# powerblade_4v0.net
KiCad netlist of a schematic drawn in EAGLE
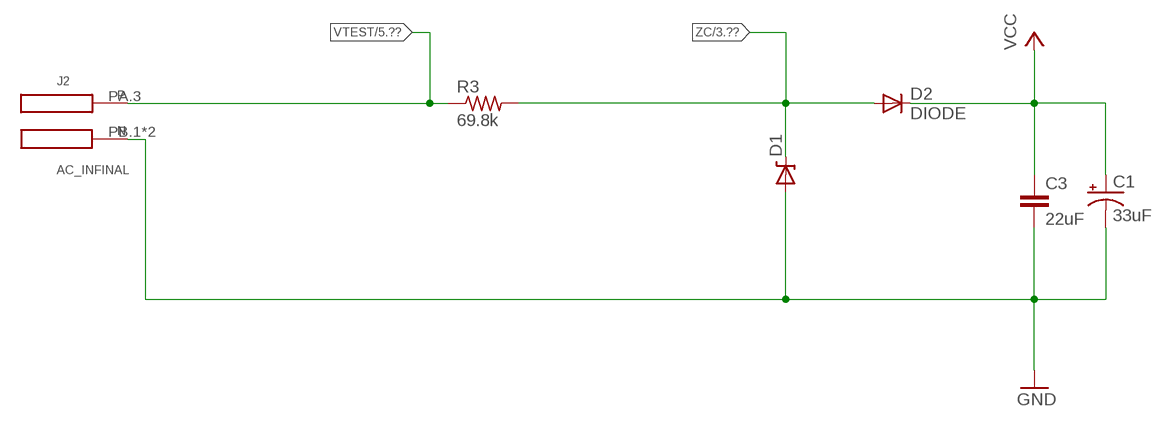
[diagram p0: schematic, sheet 1]
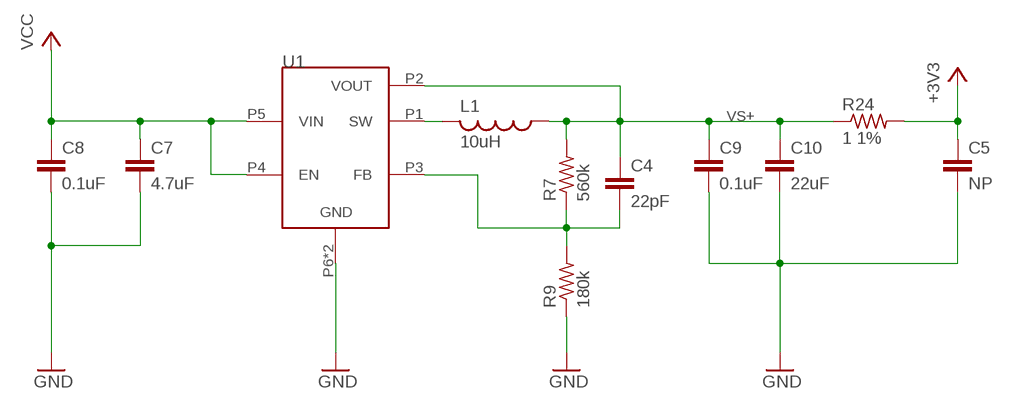
[diagram p1: schematic, sheet 2]
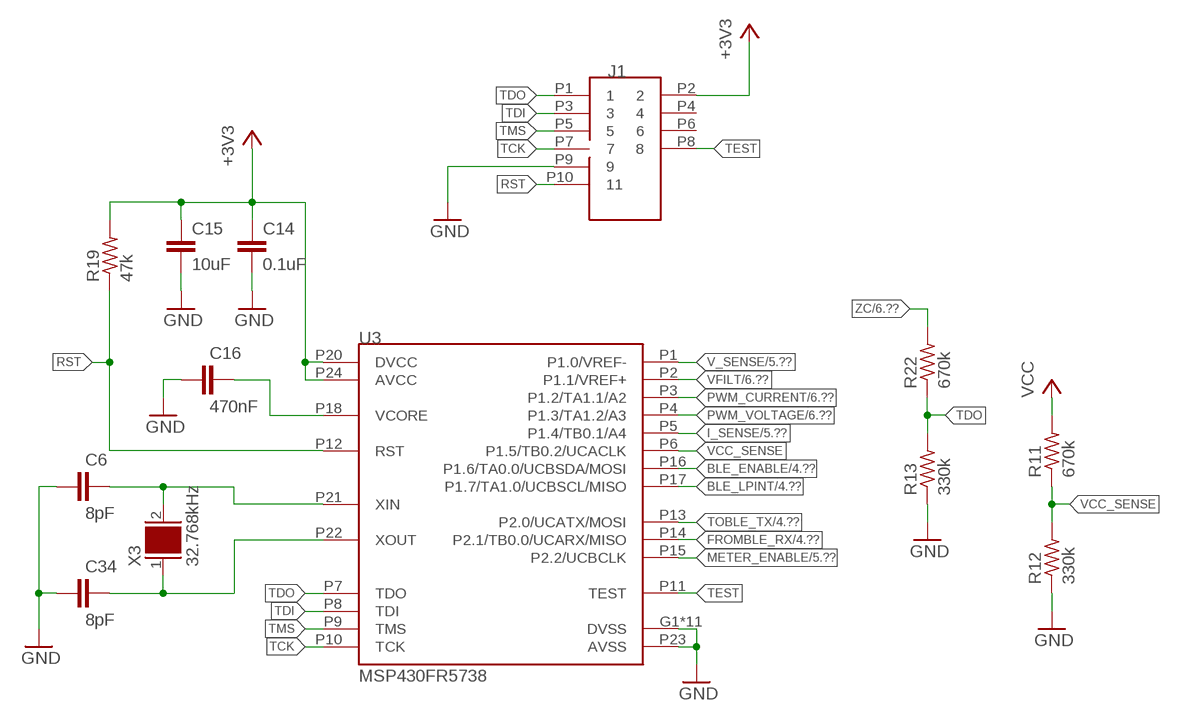
[diagram p2: schematic, sheet 3]
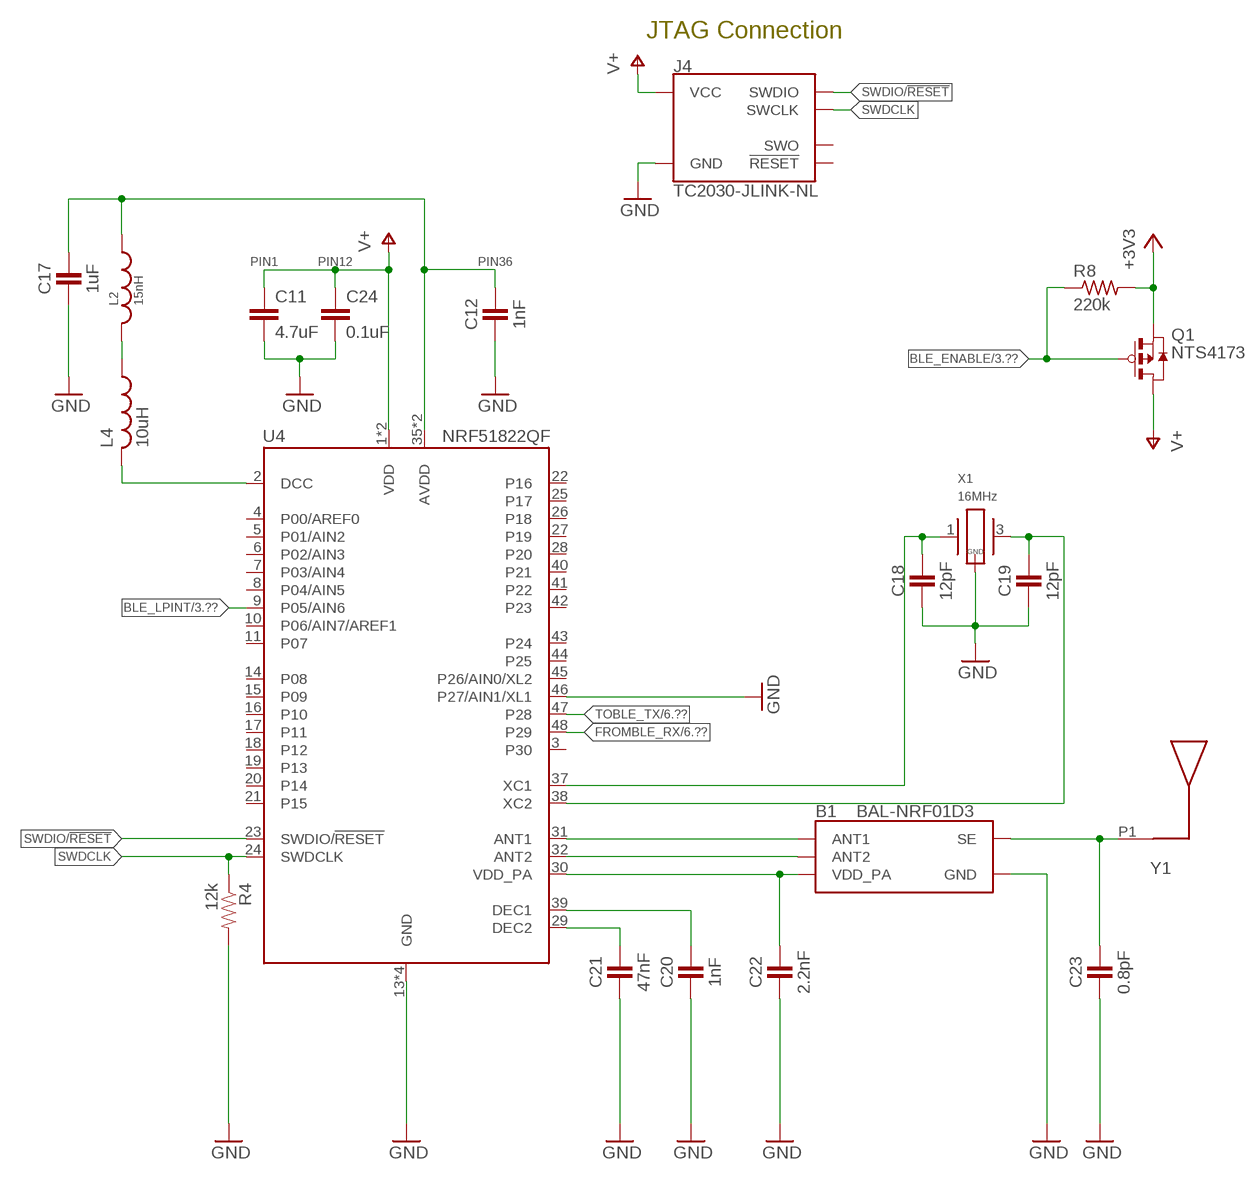
[diagram p3: schematic, sheet 4]
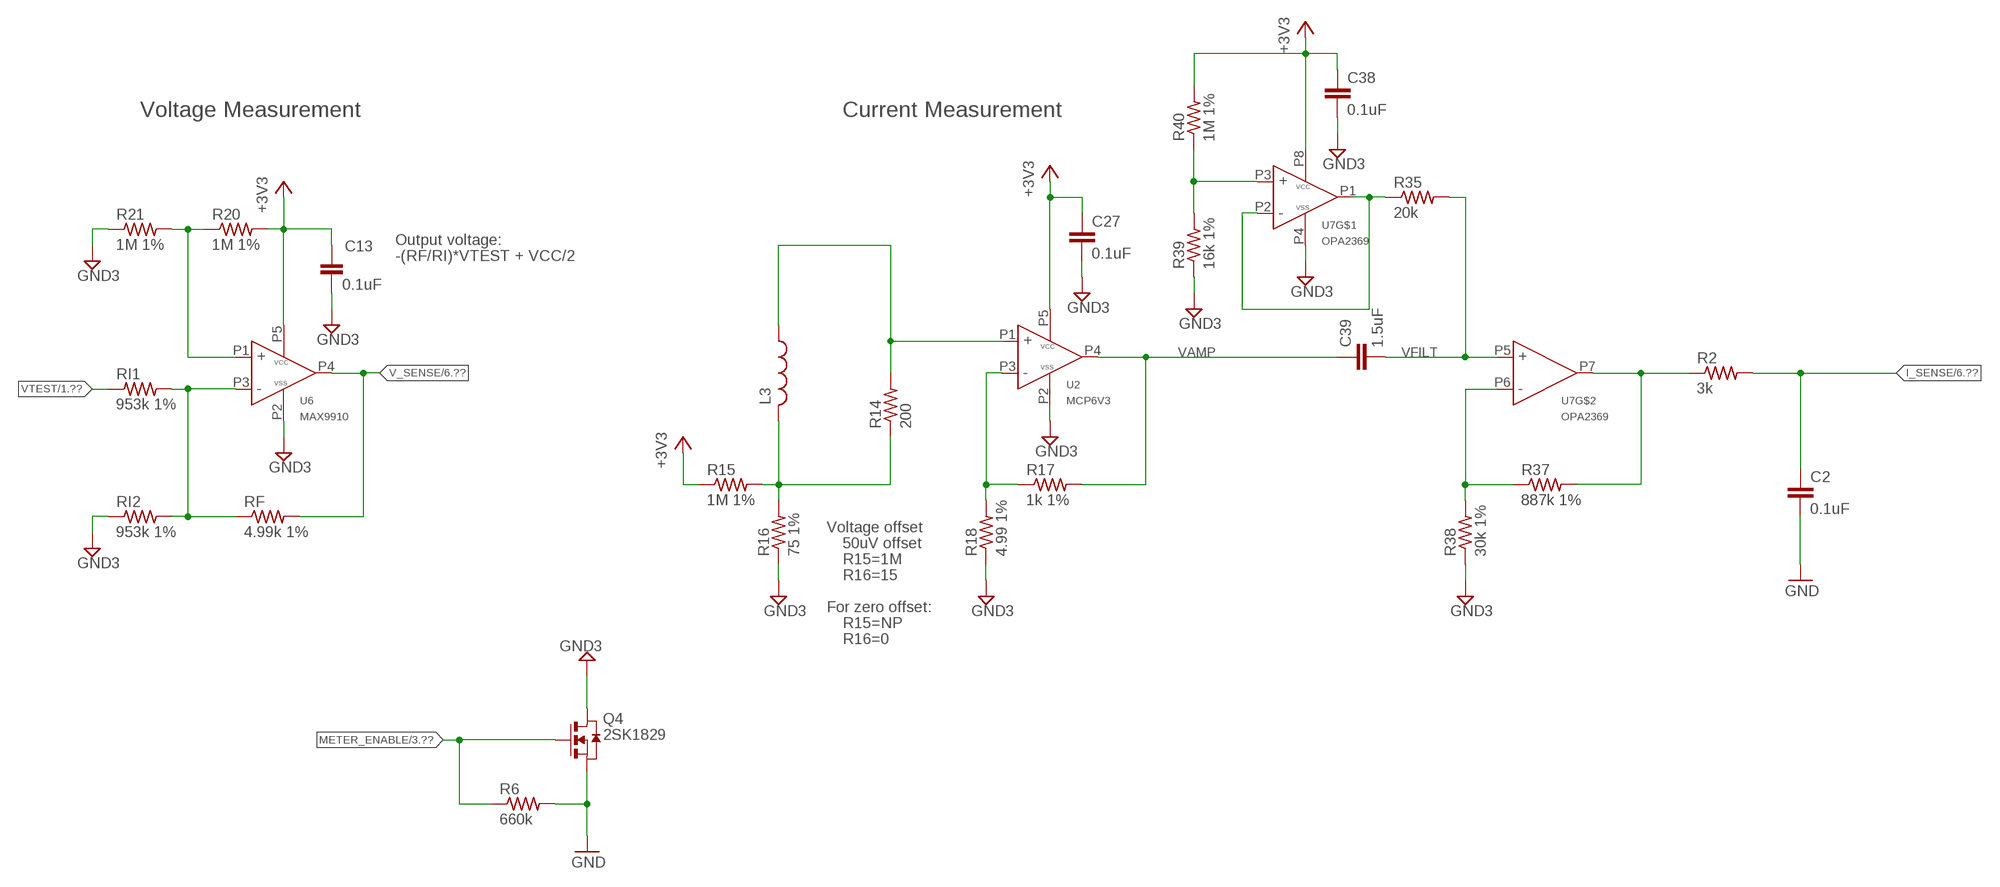
[diagram p4: schematic, sheet 5]
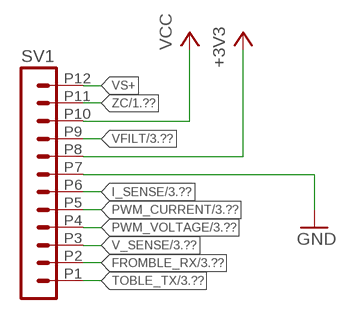
[diagram p5: schematic, sheet 6]

(export (version "E")
  (design (tool "Eeschema 10.0.6"))
  (components
    (comp (ref "C2")
      (value "0.1uF")
      (footprint "eagle-import:C0402")
      (libsource (lib "eagle-import") (part "C-EUC0402"))
    )
    (comp (ref "C13")
      (value "0.1uF")
      (footprint "eagle-import:0402_CAP")
      (libsource (lib "eagle-import") (part "CAPACITOR"))
    )
    (comp (ref "C27")
      (value "0.1uF")
      (footprint "eagle-import:C0402")
      (libsource (lib "eagle-import") (part "C-EUC0402"))
    )
    (comp (ref "C38")
      (value "0.1uF")
      (footprint "eagle-import:C0402")
      (libsource (lib "eagle-import") (part "C-EUC0402"))
    )
    (comp (ref "C39")
      (value "1.5uF")
      (footprint "eagle-import:C0402")
      (libsource (lib "eagle-import") (part "C-EUC0402"))
    )
    (comp (ref "L3")
      (value "L-USL0805")
      (footprint "eagle-import:L0805")
      (libsource (lib "eagle-import") (part "L-USL0805"))
    )
    (comp (ref "Q4")
      (value "2SK1829")
      (footprint "eagle-import:SC-70-3")
      (libsource (lib "eagle-import") (part "2SK1829"))
    )
    (comp (ref "R2")
      (value "3k")
      (footprint "eagle-import:R0402_SM")
      (libsource (lib "eagle-import") (part "R-US_R0402_SM"))
    )
    (comp (ref "R6")
      (value "660k")
      (footprint "eagle-import:R0402")
      (libsource (lib "eagle-import") (part "R-US_R0402"))
    )
    (comp (ref "R14")
      (value "200")
      (footprint "eagle-import:R0402")
      (libsource (lib "eagle-import") (part "R-US_R0402"))
    )
    (comp (ref "R15")
      (value "1M 1%")
      (footprint "eagle-import:R0402")
      (libsource (lib "eagle-import") (part "R-US_R0402"))
    )
    (comp (ref "R16")
      (value "75 1%")
      (footprint "eagle-import:R0402")
      (libsource (lib "eagle-import") (part "R-US_R0402"))
    )
    (comp (ref "R17")
      (value "1k 1%")
      (footprint "eagle-import:R0402")
      (libsource (lib "eagle-import") (part "R-US_R0402"))
    )
    (comp (ref "R18")
      (value "4.99 1%")
      (footprint "eagle-import:R0402")
      (libsource (lib "eagle-import") (part "R-US_R0402"))
    )
    (comp (ref "R20")
      (value "1M 1%")
      (footprint "eagle-import:R0402")
      (libsource (lib "eagle-import") (part "R-US_R0402"))
    )
    (comp (ref "R21")
      (value "1M 1%")
      (footprint "eagle-import:R0402_SM")
      (libsource (lib "eagle-import") (part "R-US_R0402_SM"))
    )
    (comp (ref "R35")
      (value "20k")
      (footprint "eagle-import:R0402")
      (libsource (lib "eagle-import") (part "R-US_R0402"))
    )
    (comp (ref "R37")
      (value "887k 1%")
      (footprint "eagle-import:R0402")
      (libsource (lib "eagle-import") (part "R-US_R0402"))
    )
    (comp (ref "R38")
      (value "30k 1%")
      (footprint "eagle-import:R0402")
      (libsource (lib "eagle-import") (part "R-US_R0402"))
    )
    (comp (ref "R39")
      (value "16k 1%")
      (footprint "eagle-import:R0402")
      (libsource (lib "eagle-import") (part "R-US_R0402"))
    )
    (comp (ref "R40")
      (value "1M 1%")
      (footprint "eagle-import:R0402")
      (libsource (lib "eagle-import") (part "R-US_R0402"))
    )
    (comp (ref "RF")
      (value "4.99k 1%")
      (footprint "eagle-import:R0402")
      (libsource (lib "eagle-import") (part "R-US_R0402"))
    )
    (comp (ref "RI1")
      (value "953k 1%")
      (footprint "eagle-import:R0402")
      (libsource (lib "eagle-import") (part "R-US_R0402"))
    )
    (comp (ref "RI2")
      (value "953k 1%")
      (footprint "eagle-import:R0402")
      (libsource (lib "eagle-import") (part "R-US_R0402"))
    )
    (comp (ref "U2")
      (value "MCP6V3")
      (footprint "eagle-import:SC70-5")
      (fields (field (name "DIGIKEY") "296-19547-1-ND"))
      (libsource (lib "eagle-import") (part "MCP6V3"))
    )
    (comp (ref "U6")
      (value "MAX9910")
      (footprint "eagle-import:SC70-5")
      (fields (field (name "DIGIKEY") "296-25252-1-ND"))
      (libsource (lib "eagle-import") (part "MAX9910"))
    )
    (comp (ref "U7")
      (value "OPA2369")
      (footprint "eagle-import:SOT-23-8")
      (libsource (lib "eagle-import") (part "OPA2369"))
    )
    (comp (ref "C6")
      (value "8pF")
      (footprint "eagle-import:C0402")
      (libsource (lib "eagle-import") (part "C-EUC0402"))
    )
    (comp (ref "C14")
      (value "0.1uF")
      (footprint "eagle-import:C0402")
      (libsource (lib "eagle-import") (part "C-EUC0402"))
    )
    (comp (ref "C15")
      (value "10uF")
      (footprint "eagle-import:C0603_SM")
      (libsource (lib "eagle-import") (part "C-EUC0603_SM"))
    )
    (comp (ref "C16")
      (value "470nF")
      (footprint "eagle-import:C0402")
      (libsource (lib "eagle-import") (part "C-EUC0402"))
    )
    (comp (ref "C34")
      (value "8pF")
      (footprint "eagle-import:C0402")
      (libsource (lib "eagle-import") (part "C-EUC0402"))
    )
    (comp (ref "J1")
      (value "JTAG_14PIN_IDC-ND")
      (footprint "eagle-import:TC2050-IDC-NL-430-ND")
      (libsource (lib "eagle-import") (part "JTAG_14PIN_IDC-ND"))
    )
    (comp (ref "R11")
      (value "670k")
      (footprint "eagle-import:R0402")
      (libsource (lib "eagle-import") (part "R-US_R0402"))
    )
    (comp (ref "R12")
      (value "330k")
      (footprint "eagle-import:R0402")
      (libsource (lib "eagle-import") (part "R-US_R0402"))
    )
    (comp (ref "R13")
      (value "330k")
      (footprint "eagle-import:R0402")
      (libsource (lib "eagle-import") (part "R-US_R0402"))
    )
    (comp (ref "R19")
      (value "47k")
      (footprint "eagle-import:R0402")
      (libsource (lib "eagle-import") (part "R-US_R0402"))
    )
    (comp (ref "R22")
      (value "670k")
      (footprint "eagle-import:R0402")
      (libsource (lib "eagle-import") (part "R-US_R0402"))
    )
    (comp (ref "U3")
      (value "MSP430FR5738")
      (footprint "eagle-import:VQFN-24")
      (libsource (lib "eagle-import") (part "MSP430FR5738"))
    )
    (comp (ref "X3")
      (value "32.768kHz")
      (footprint "eagle-import:0805")
      (libsource (lib "eagle-import") (part "CRYSTAL_0805"))
    )
    (comp (ref "B1")
      (value "BAL-NRF01D3")
      (footprint "eagle-import:BAL-NRF01D3")
      (libsource (lib "eagle-import") (part "BAL-NRF01D3"))
    )
    (comp (ref "C11")
      (value "4.7uF")
      (footprint "eagle-import:C0402")
      (libsource (lib "eagle-import") (part "C-EUC0402"))
    )
    (comp (ref "C12")
      (value "1nF")
      (footprint "eagle-import:0402_CAP")
      (libsource (lib "eagle-import") (part "CAPACITOR"))
    )
    (comp (ref "C17")
      (value "1uF")
      (footprint "eagle-import:0402_CAP")
      (libsource (lib "eagle-import") (part "CAPACITOR"))
    )
    (comp (ref "C18")
      (value "12pF")
      (footprint "eagle-import:0402_CAP")
      (libsource (lib "eagle-import") (part "CAPACITOR"))
    )
    (comp (ref "C19")
      (value "12pF")
      (footprint "eagle-import:0402_CAP")
      (libsource (lib "eagle-import") (part "CAPACITOR"))
    )
    (comp (ref "C20")
      (value "1nF")
      (footprint "eagle-import:0402_CAP")
      (libsource (lib "eagle-import") (part "CAPACITOR"))
    )
    (comp (ref "C21")
      (value "47nF")
      (footprint "eagle-import:0402_CAP")
      (libsource (lib "eagle-import") (part "CAPACITOR"))
    )
    (comp (ref "C22")
      (value "2.2nF")
      (footprint "eagle-import:0402_CAP")
      (libsource (lib "eagle-import") (part "CAPACITOR"))
    )
    (comp (ref "C23")
      (value "0.8pF")
      (footprint "eagle-import:0402_CAP")
      (libsource (lib "eagle-import") (part "CAPACITOR"))
    )
    (comp (ref "C24")
      (value "0.1uF")
      (footprint "eagle-import:C0402")
      (libsource (lib "eagle-import") (part "C-EUC0402"))
    )
    (comp (ref "J4")
      (value "TC2030-JLINK-NL")
      (footprint "eagle-import:TC2030-IDC-NL")
      (libsource (lib "eagle-import") (part "TC2030-JLINK-NL"))
    )
    (comp (ref "L2")
      (value "15nH")
      (footprint "eagle-import:0402_CAP")
      (libsource (lib "eagle-import") (part "INDUCTOR0402"))
    )
    (comp (ref "L4")
      (value "10uH")
      (footprint "eagle-import:C0603_TN")
      (libsource (lib "eagle-import") (part "L-USL0603_TN"))
    )
    (comp (ref "Q1")
      (value "NTS4173")
      (footprint "eagle-import:SC-70-3")
      (libsource (lib "eagle-import") (part "NTS4173"))
    )
    (comp (ref "R4")
      (value "12k")
      (footprint "eagle-import:0402_RES")
      (libsource (lib "eagle-import") (part "RESISTOR"))
    )
    (comp (ref "R8")
      (value "220k")
      (footprint "eagle-import:R0402_SM")
      (libsource (lib "eagle-import") (part "R-US_R0402_SM"))
    )
    (comp (ref "U4")
      (value "NRF51822QF")
      (footprint "eagle-import:QFN-48-6MM")
      (libsource (lib "eagle-import") (part "NRF51822QF"))
    )
    (comp (ref "X1")
      (value "16MHz")
      (footprint "eagle-import:TXC-8Y")
      (libsource (lib "eagle-import") (part "TXC-8Y"))
    )
    (comp (ref "Y1")
      (value "UREACH_XTEND")
      (footprint "eagle-import:UREACH_XTEND")
      (libsource (lib "eagle-import") (part "UREACH_XTEND"))
    )
    (comp (ref "SV1")
      (value "MA12-11M27")
      (footprint "eagle-import:MA12-1_1MM27")
      (libsource (lib "eagle-import") (part "MA12-11M27"))
    )
    (comp (ref "C4")
      (value "22pF")
      (footprint "eagle-import:C0402")
      (libsource (lib "eagle-import") (part "C-EUC0402"))
    )
    (comp (ref "C5")
      (value "NP")
      (footprint "eagle-import:C0603_TN")
      (libsource (lib "eagle-import") (part "C-EUC0603_TN"))
    )
    (comp (ref "C7")
      (value "4.7uF")
      (footprint "eagle-import:C0402")
      (libsource (lib "eagle-import") (part "C-EUC0402"))
    )
    (comp (ref "C8")
      (value "0.1uF")
      (footprint "eagle-import:C0402")
      (libsource (lib "eagle-import") (part "C-EUC0402"))
    )
    (comp (ref "C9")
      (value "0.1uF")
      (footprint "eagle-import:C0402_SM")
      (libsource (lib "eagle-import") (part "C-EUC0402_SM"))
    )
    (comp (ref "C10")
      (value "22uF")
      (footprint "eagle-import:C0603_SM")
      (libsource (lib "eagle-import") (part "C-EUC0603_SM"))
    )
    (comp (ref "L1")
      (value "10uH")
      (footprint "eagle-import:L0805")
      (libsource (lib "eagle-import") (part "L-USL0805"))
    )
    (comp (ref "R7")
      (value "560k")
      (footprint "eagle-import:R0402")
      (libsource (lib "eagle-import") (part "R-US_R0402"))
    )
    (comp (ref "R9")
      (value "180k")
      (footprint "eagle-import:R0402")
      (libsource (lib "eagle-import") (part "R-US_R0402"))
    )
    (comp (ref "R24")
      (value "1 1%")
      (footprint "eagle-import:R0603_SM")
      (libsource (lib "eagle-import") (part "R-US_R0603_SM"))
    )
    (comp (ref "U1")
      (value "TPS62122")
      (footprint "eagle-import:WDFN-6")
      (libsource (lib "eagle-import") (part "TPS62122"))
    )
    (comp (ref "C1")
      (value "33uF")
      (footprint "eagle-import:CPOL0805_SM")
      (libsource (lib "eagle-import") (part "CPOL-US0805_SM"))
    )
    (comp (ref "C3")
      (value "22uF")
      (footprint "eagle-import:C0603_SM")
      (libsource (lib "eagle-import") (part "C-EUC0603_SM"))
    )
    (comp (ref "D1")
      (value "ZENERBZT52")
      (footprint "eagle-import:BZT52")
      (fields (field (name "DIGIKEY") "BZT52C10T-7DICT-ND "))
      (libsource (lib "eagle-import") (part "ZENERBZT52"))
    )
    (comp (ref "D2")
      (value "DIODE")
      (footprint "eagle-import:BAS521")
      (libsource (lib "eagle-import") (part "DIODE"))
    )
    (comp (ref "J2")
      (value "AC_INFINAL")
      (footprint "eagle-import:AC3_FINAL")
      (libsource (lib "eagle-import") (part "AC_INFINAL"))
    )
    (comp (ref "R3")
      (value "69.8k")
      (footprint "eagle-import:R1210")
      (libsource (lib "eagle-import") (part "R-US_R1210"))
    )
  )
  (nets
    (net (code "1") (name "+3V3") (class "Default")
      (node (ref "C13") (pin "1") (pinfunction "1_1") (pintype "bidirectional"))
      (node (ref "C14") (pin "1") (pinfunction "1_1") (pintype "passive"))
      (node (ref "C15") (pin "1") (pinfunction "1_1") (pintype "passive"))
      (node (ref "C27") (pin "1") (pinfunction "1_1") (pintype "passive"))
      (node (ref "C38") (pin "1") (pinfunction "1_1") (pintype "passive"))
      (node (ref "C5") (pin "1") (pinfunction "1_1") (pintype "passive"))
      (node (ref "J1") (pin "P2") (pinfunction "2_P2") (pintype "bidirectional"))
      (node (ref "Q1") (pin "P2") (pinfunction "S_P2") (pintype "passive"))
      (node (ref "R15") (pin "1") (pinfunction "1_1") (pintype "passive"))
      (node (ref "R19") (pin "2") (pinfunction "2_2") (pintype "passive"))
      (node (ref "R20") (pin "2") (pinfunction "2_2") (pintype "passive"))
      (node (ref "R24") (pin "2") (pinfunction "2_2") (pintype "passive"))
      (node (ref "R40") (pin "2") (pinfunction "2_2") (pintype "passive"))
      (node (ref "R8") (pin "2") (pinfunction "2_2") (pintype "passive"))
      (node (ref "SV1") (pin "P8") (pinfunction "8_P8") (pintype "passive"))
      (node (ref "U2") (pin "P5") (pinfunction "VCC_P5") (pintype "bidirectional"))
      (node (ref "U3") (pin "P20") (pinfunction "DVCC_P20") (pintype "bidirectional"))
      (node (ref "U3") (pin "P24") (pinfunction "AVCC_P24") (pintype "bidirectional"))
      (node (ref "U6") (pin "P5") (pinfunction "VCC_P5") (pintype "bidirectional"))
      (node (ref "U7") (pin "P8") (pinfunction "VCC_P8") (pintype "bidirectional"))
    )
    (net (code "2") (name "BLE_ENABLE") (class "Default")
      (node (ref "Q1") (pin "P1") (pinfunction "G_P1") (pintype "passive"))
      (node (ref "R8") (pin "1") (pinfunction "1_1") (pintype "passive"))
      (node (ref "U3") (pin "P16") (pinfunction "P1.6/TA0.0/UCBSDA/MOSI_P16") (pintype "bidirectional"))
    )
    (net (code "3") (name "BLE_LPINT") (class "Default")
      (node (ref "U3") (pin "P17") (pinfunction "P1.7/TA1.0/UCBSCL/MISO_P17") (pintype "bidirectional"))
      (node (ref "U4") (pin "9") (pinfunction "P05/AIN6_9") (pintype "bidirectional"))
    )
    (net (code "4") (name "FROMBLE_RX") (class "Default")
      (node (ref "SV1") (pin "P2") (pinfunction "2_P2") (pintype "passive"))
      (node (ref "U3") (pin "P14") (pinfunction "P2.1/TB0.0/UCARX/MISO_P14") (pintype "bidirectional"))
      (node (ref "U4") (pin "48") (pinfunction "P29_48") (pintype "bidirectional"))
    )
    (net (code "5") (name "GND") (class "Default")
      (node (ref "B1") (pin "GND") (pinfunction "GND_GND") (pintype "bidirectional"))
      (node (ref "C1") (pin "-") (pinfunction "-_-") (pintype "passive"))
      (node (ref "C10") (pin "2") (pinfunction "2_2") (pintype "passive"))
      (node (ref "C11") (pin "2") (pinfunction "2_2") (pintype "passive"))
      (node (ref "C12") (pin "2") (pinfunction "2_2") (pintype "bidirectional"))
      (node (ref "C14") (pin "2") (pinfunction "2_2") (pintype "passive"))
      (node (ref "C15") (pin "2") (pinfunction "2_2") (pintype "passive"))
      (node (ref "C16") (pin "1") (pinfunction "1_1") (pintype "passive"))
      (node (ref "C17") (pin "2") (pinfunction "2_2") (pintype "bidirectional"))
      (node (ref "C18") (pin "2") (pinfunction "2_2") (pintype "bidirectional"))
      (node (ref "C19") (pin "2") (pinfunction "2_2") (pintype "bidirectional"))
      (node (ref "C2") (pin "2") (pinfunction "2_2") (pintype "passive"))
      (node (ref "C20") (pin "2") (pinfunction "2_2") (pintype "bidirectional"))
      (node (ref "C21") (pin "2") (pinfunction "2_2") (pintype "bidirectional"))
      (node (ref "C22") (pin "2") (pinfunction "2_2") (pintype "bidirectional"))
      (node (ref "C23") (pin "2") (pinfunction "2_2") (pintype "bidirectional"))
      (node (ref "C24") (pin "2") (pinfunction "2_2") (pintype "passive"))
      (node (ref "C3") (pin "2") (pinfunction "2_2") (pintype "passive"))
      (node (ref "C34") (pin "1") (pinfunction "1_1") (pintype "passive"))
      (node (ref "C5") (pin "2") (pinfunction "2_2") (pintype "passive"))
      (node (ref "C6") (pin "1") (pinfunction "1_1") (pintype "passive"))
      (node (ref "C7") (pin "2") (pinfunction "2_2") (pintype "passive"))
      (node (ref "C8") (pin "2") (pinfunction "2_2") (pintype "passive"))
      (node (ref "C9") (pin "2") (pinfunction "2_2") (pintype "passive"))
      (node (ref "D1") (pin "A") (pinfunction "A_A") (pintype "passive"))
      (node (ref "J1") (pin "P9") (pinfunction "9_P9") (pintype "bidirectional"))
      (node (ref "J2") (pin "PB.1") (pinfunction "N_PB.1") (pintype "bidirectional"))
      (node (ref "J2") (pin "PB.3") (pinfunction "N_PB.3") (pintype "bidirectional"))
      (node (ref "J4") (pin "5") (pinfunction "GND_5") (pintype "bidirectional"))
      (node (ref "Q4") (pin "P2") (pinfunction "S_P2") (pintype "passive"))
      (node (ref "R12") (pin "1") (pinfunction "1_1") (pintype "passive"))
      (node (ref "R13") (pin "1") (pinfunction "1_1") (pintype "passive"))
      (node (ref "R4") (pin "2") (pinfunction "2_2") (pintype "passive"))
      (node (ref "R6") (pin "2") (pinfunction "2_2") (pintype "passive"))
      (node (ref "R9") (pin "1") (pinfunction "1_1") (pintype "passive"))
      (node (ref "SV1") (pin "P7") (pinfunction "7_P7") (pintype "passive"))
      (node (ref "U1") (pin "P6") (pinfunction "GND_P6") (pintype "bidirectional"))
      (node (ref "U1") (pin "PAD") (pinfunction "GND_PAD") (pintype "bidirectional"))
      (node (ref "U3") (pin "G1") (pinfunction "DVSS_G1") (pintype "bidirectional"))
      (node (ref "U3") (pin "G2") (pinfunction "DVSS_G2") (pintype "bidirectional"))
      (node (ref "U3") (pin "G3") (pinfunction "DVSS_G3") (pintype "bidirectional"))
      (node (ref "U3") (pin "G4") (pinfunction "DVSS_G4") (pintype "bidirectional"))
      (node (ref "U3") (pin "G5") (pinfunction "DVSS_G5") (pintype "bidirectional"))
      (node (ref "U3") (pin "G6") (pinfunction "DVSS_G6") (pintype "bidirectional"))
      (node (ref "U3") (pin "G7") (pinfunction "DVSS_G7") (pintype "bidirectional"))
      (node (ref "U3") (pin "G8") (pinfunction "DVSS_G8") (pintype "bidirectional"))
      (node (ref "U3") (pin "G9") (pinfunction "DVSS_G9") (pintype "bidirectional"))
      (node (ref "U3") (pin "P19") (pinfunction "DVSS_P19") (pintype "bidirectional"))
      (node (ref "U3") (pin "P23") (pinfunction "AVSS_P23") (pintype "bidirectional"))
      (node (ref "U3") (pin "PAD") (pinfunction "DVSS_PAD") (pintype "bidirectional"))
      (node (ref "U4") (pin "13") (pinfunction "GND_13") (pintype "bidirectional"))
      (node (ref "U4") (pin "33") (pinfunction "GND_33") (pintype "bidirectional"))
      (node (ref "U4") (pin "34") (pinfunction "GND_34") (pintype "bidirectional"))
      (node (ref "U4") (pin "46") (pinfunction "P27/AIN1/XL1_46") (pintype "bidirectional"))
      (node (ref "U4") (pin "GND") (pinfunction "GND_GND") (pintype "bidirectional"))
      (node (ref "X1") (pin "2") (pinfunction "GND_2") (pintype "bidirectional"))
      (node (ref "X1") (pin "4") (pinfunction "GND_4") (pintype "bidirectional"))
    )
    (net (code "6") (name "GND3") (class "Default")
      (node (ref "C13") (pin "2") (pinfunction "2_2") (pintype "bidirectional"))
      (node (ref "C27") (pin "2") (pinfunction "2_2") (pintype "passive"))
      (node (ref "C38") (pin "2") (pinfunction "2_2") (pintype "passive"))
      (node (ref "Q4") (pin "P3") (pinfunction "D_P3") (pintype "passive"))
      (node (ref "R16") (pin "1") (pinfunction "1_1") (pintype "passive"))
      (node (ref "R18") (pin "1") (pinfunction "1_1") (pintype "passive"))
      (node (ref "R21") (pin "1") (pinfunction "1_1") (pintype "passive"))
      (node (ref "R38") (pin "1") (pinfunction "1_1") (pintype "passive"))
      (node (ref "R39") (pin "1") (pinfunction "1_1") (pintype "passive"))
      (node (ref "RI2") (pin "1") (pinfunction "1_1") (pintype "passive"))
      (node (ref "U2") (pin "P2") (pinfunction "VSS_P2") (pintype "bidirectional"))
      (node (ref "U6") (pin "P2") (pinfunction "VSS_P2") (pintype "bidirectional"))
      (node (ref "U7") (pin "P4") (pinfunction "VSS_P4") (pintype "bidirectional"))
    )
    (net (code "7") (name "I_SENSE") (class "Default")
      (node (ref "C2") (pin "1") (pinfunction "1_1") (pintype "passive"))
      (node (ref "R2") (pin "2") (pinfunction "2_2") (pintype "passive"))
      (node (ref "SV1") (pin "P6") (pinfunction "6_P6") (pintype "passive"))
      (node (ref "U3") (pin "P5") (pinfunction "P1.4/TB0.1/A4_P5") (pintype "bidirectional"))
    )
    (net (code "8") (name "METER_ENABLE") (class "Default")
      (node (ref "Q4") (pin "P1") (pinfunction "G_P1") (pintype "passive"))
      (node (ref "R6") (pin "1") (pinfunction "1_1") (pintype "passive"))
      (node (ref "U3") (pin "P15") (pinfunction "P2.2/UCBCLK_P15") (pintype "bidirectional"))
    )
    (net (code "9") (name "Net-(B1-PadSE)") (class "Default")
      (node (ref "B1") (pin "SE") (pinfunction "SE_SE") (pintype "bidirectional"))
      (node (ref "C23") (pin "1") (pinfunction "1_1") (pintype "bidirectional"))
      (node (ref "Y1") (pin "P1") (pinfunction "P1_P1") (pintype "bidirectional"))
    )
    (net (code "10") (name "Net-(B1-VDD_PA)") (class "Default")
      (node (ref "B1") (pin "VCC") (pinfunction "VDD_PA_VCC") (pintype "bidirectional"))
      (node (ref "C22") (pin "1") (pinfunction "1_1") (pintype "bidirectional"))
      (node (ref "U4") (pin "30") (pinfunction "VDD_PA_30") (pintype "bidirectional"))
    )
    (net (code "11") (name "Net-(C12-Pad1)") (class "Default")
      (node (ref "C12") (pin "1") (pinfunction "1_1") (pintype "bidirectional"))
      (node (ref "C17") (pin "1") (pinfunction "1_1") (pintype "bidirectional"))
      (node (ref "L2") (pin "1") (pinfunction "1_1") (pintype "bidirectional"))
      (node (ref "U4") (pin "35") (pinfunction "AVDD_35") (pintype "bidirectional"))
      (node (ref "U4") (pin "36") (pinfunction "AVDD_36") (pintype "bidirectional"))
    )
    (net (code "12") (name "Net-(L2-Pad2)") (class "Default")
      (node (ref "L2") (pin "2") (pinfunction "2_2") (pintype "bidirectional"))
      (node (ref "L4") (pin "1") (pinfunction "1_1") (pintype "passive"))
    )
    (net (code "13") (name "Net-(L3-Pad2)") (class "Default")
      (node (ref "L3") (pin "2") (pinfunction "2_2") (pintype "passive"))
      (node (ref "R14") (pin "1") (pinfunction "1_1") (pintype "passive"))
      (node (ref "R15") (pin "2") (pinfunction "2_2") (pintype "passive"))
      (node (ref "R16") (pin "2") (pinfunction "2_2") (pintype "passive"))
    )
    (net (code "14") (name "Net-(U1-FB)") (class "Default")
      (node (ref "C4") (pin "2") (pinfunction "2_2") (pintype "passive"))
      (node (ref "R7") (pin "1") (pinfunction "1_1") (pintype "passive"))
      (node (ref "R9") (pin "2") (pinfunction "2_2") (pintype "passive"))
      (node (ref "U1") (pin "P3") (pinfunction "FB_P3") (pintype "bidirectional"))
    )
    (net (code "15") (name "Net-(U1-SW)") (class "Default")
      (node (ref "L1") (pin "2") (pinfunction "2_2") (pintype "passive"))
      (node (ref "U1") (pin "P1") (pinfunction "SW_P1") (pintype "bidirectional"))
    )
    (net (code "16") (name "Net-(U2-IN+)") (class "Default")
      (node (ref "L3") (pin "1") (pinfunction "1_1") (pintype "passive"))
      (node (ref "R14") (pin "2") (pinfunction "2_2") (pintype "passive"))
      (node (ref "U2") (pin "P1") (pinfunction "IN+_P1") (pintype "bidirectional"))
    )
    (net (code "17") (name "Net-(U2-IN-)") (class "Default")
      (node (ref "R17") (pin "1") (pinfunction "1_1") (pintype "passive"))
      (node (ref "R18") (pin "2") (pinfunction "2_2") (pintype "passive"))
      (node (ref "U2") (pin "P3") (pinfunction "IN-_P3") (pintype "bidirectional"))
    )
    (net (code "18") (name "Net-(U3-VCORE)") (class "Default")
      (node (ref "C16") (pin "2") (pinfunction "2_2") (pintype "passive"))
      (node (ref "U3") (pin "P18") (pinfunction "VCORE_P18") (pintype "bidirectional"))
    )
    (net (code "19") (name "Net-(U3-XIN)") (class "Default")
      (node (ref "C6") (pin "2") (pinfunction "2_2") (pintype "passive"))
      (node (ref "U3") (pin "P21") (pinfunction "XIN_P21") (pintype "bidirectional"))
      (node (ref "X3") (pin "2") (pinfunction "P2_2") (pintype "bidirectional"))
    )
    (net (code "20") (name "Net-(U3-XOUT)") (class "Default")
      (node (ref "C34") (pin "2") (pinfunction "2_2") (pintype "passive"))
      (node (ref "U3") (pin "P22") (pinfunction "XOUT_P22") (pintype "bidirectional"))
      (node (ref "X3") (pin "1") (pinfunction "P1_1") (pintype "bidirectional"))
    )
    (net (code "21") (name "Net-(U4-ANT1)") (class "Default")
      (node (ref "B1") (pin "ANT1") (pinfunction "ANT1_ANT1") (pintype "bidirectional"))
      (node (ref "U4") (pin "31") (pinfunction "ANT1_31") (pintype "bidirectional"))
    )
    (net (code "22") (name "Net-(U4-ANT2)") (class "Default")
      (node (ref "B1") (pin "ANT2") (pinfunction "ANT2_ANT2") (pintype "bidirectional"))
      (node (ref "U4") (pin "32") (pinfunction "ANT2_32") (pintype "bidirectional"))
    )
    (net (code "23") (name "Net-(U4-DCC)") (class "Default")
      (node (ref "L4") (pin "2") (pinfunction "2_2") (pintype "passive"))
      (node (ref "U4") (pin "2") (pinfunction "DCC_2") (pintype "bidirectional"))
    )
    (net (code "24") (name "Net-(U4-DEC1)") (class "Default")
      (node (ref "C20") (pin "1") (pinfunction "1_1") (pintype "bidirectional"))
      (node (ref "U4") (pin "39") (pinfunction "DEC1_39") (pintype "bidirectional"))
    )
    (net (code "25") (name "Net-(U4-DEC2)") (class "Default")
      (node (ref "C21") (pin "1") (pinfunction "1_1") (pintype "bidirectional"))
      (node (ref "U4") (pin "29") (pinfunction "DEC2_29") (pintype "bidirectional"))
    )
    (net (code "26") (name "Net-(U4-XC1)") (class "Default")
      (node (ref "C18") (pin "1") (pinfunction "1_1") (pintype "bidirectional"))
      (node (ref "U4") (pin "37") (pinfunction "XC1_37") (pintype "bidirectional"))
      (node (ref "X1") (pin "1") (pinfunction "1_1") (pintype "bidirectional"))
    )
    (net (code "27") (name "Net-(U4-XC2)") (class "Default")
      (node (ref "C19") (pin "1") (pinfunction "1_1") (pintype "bidirectional"))
      (node (ref "U4") (pin "38") (pinfunction "XC2_38") (pintype "bidirectional"))
      (node (ref "X1") (pin "3") (pinfunction "2_3") (pintype "bidirectional"))
    )
    (net (code "28") (name "Net-(U6-IN+)") (class "Default")
      (node (ref "R20") (pin "1") (pinfunction "1_1") (pintype "passive"))
      (node (ref "R21") (pin "2") (pinfunction "2_2") (pintype "passive"))
      (node (ref "U6") (pin "P1") (pinfunction "IN+_P1") (pintype "bidirectional"))
    )
    (net (code "29") (name "Net-(U6-IN-)") (class "Default")
      (node (ref "RF") (pin "1") (pinfunction "1_1") (pintype "passive"))
      (node (ref "RI1") (pin "2") (pinfunction "2_2") (pintype "passive"))
      (node (ref "RI2") (pin "2") (pinfunction "2_2") (pintype "passive"))
      (node (ref "U6") (pin "P3") (pinfunction "IN-_P3") (pintype "bidirectional"))
    )
    (net (code "30") (name "Net-(U7A-IN+)") (class "Default")
      (node (ref "R39") (pin "2") (pinfunction "2_2") (pintype "passive"))
      (node (ref "R40") (pin "1") (pinfunction "1_1") (pintype "passive"))
      (node (ref "U7") (pin "P3") (pinfunction "IN+_P3") (pintype "bidirectional"))
    )
    (net (code "31") (name "Net-(U7A-IN-)") (class "Default")
      (node (ref "R35") (pin "1") (pinfunction "1_1") (pintype "passive"))
      (node (ref "U7") (pin "P1") (pinfunction "OUT_P1") (pintype "bidirectional"))
      (node (ref "U7") (pin "P2") (pinfunction "IN-_P2") (pintype "bidirectional"))
    )
    (net (code "32") (name "Net-(U7B-IN-)") (class "Default")
      (node (ref "R37") (pin "1") (pinfunction "1_1") (pintype "passive"))
      (node (ref "R38") (pin "2") (pinfunction "2_2") (pintype "passive"))
      (node (ref "U7") (pin "P6") (pinfunction "IN-_P6") (pintype "bidirectional"))
    )
    (net (code "33") (name "Net-(U7B-OUT)") (class "Default")
      (node (ref "R2") (pin "1") (pinfunction "1_1") (pintype "passive"))
      (node (ref "R37") (pin "2") (pinfunction "2_2") (pintype "passive"))
      (node (ref "U7") (pin "P7") (pinfunction "OUT_P7") (pintype "bidirectional"))
    )
    (net (code "34") (name "PWM_CURRENT") (class "Default")
      (node (ref "SV1") (pin "P5") (pinfunction "5_P5") (pintype "passive"))
      (node (ref "U3") (pin "P3") (pinfunction "P1.2/TA1.1/A2_P3") (pintype "bidirectional"))
    )
    (net (code "35") (name "PWM_VOLTAGE") (class "Default")
      (node (ref "SV1") (pin "P4") (pinfunction "4_P4") (pintype "passive"))
      (node (ref "U3") (pin "P4") (pinfunction "P1.3/TA1.2/A3_P4") (pintype "bidirectional"))
    )
    (net (code "36") (name "RST") (class "Default")
      (node (ref "J1") (pin "P10") (pinfunction "11_P10") (pintype "bidirectional"))
      (node (ref "R19") (pin "1") (pinfunction "1_1") (pintype "passive"))
      (node (ref "U3") (pin "P12") (pinfunction "RST_P12") (pintype "bidirectional"))
    )
    (net (code "37") (name "SWDCLK") (class "Default")
      (node (ref "J4") (pin "4") (pinfunction "SWCLK_4") (pintype "bidirectional"))
      (node (ref "R4") (pin "1") (pinfunction "1_1") (pintype "passive"))
      (node (ref "U4") (pin "24") (pinfunction "SWDCLK_24") (pintype "bidirectional"))
    )
    (net (code "38") (name "SWDIO{slash}~{RESET}") (class "Default")
      (node (ref "J4") (pin "2") (pinfunction "SWDIO_2") (pintype "bidirectional"))
      (node (ref "U4") (pin "23") (pinfunction "SWDIO/~{RESET}_23") (pintype "bidirectional"))
    )
    (net (code "39") (name "TCK") (class "Default")
      (node (ref "J1") (pin "P7") (pinfunction "7_P7") (pintype "bidirectional"))
      (node (ref "U3") (pin "P10") (pinfunction "TCK_P10") (pintype "bidirectional"))
    )
    (net (code "40") (name "TDI") (class "Default")
      (node (ref "J1") (pin "P3") (pinfunction "3_P3") (pintype "bidirectional"))
      (node (ref "U3") (pin "P8") (pinfunction "TDI_P8") (pintype "bidirectional"))
    )
    (net (code "41") (name "TDO") (class "Default")
      (node (ref "J1") (pin "P1") (pinfunction "1_P1") (pintype "bidirectional"))
      (node (ref "R13") (pin "2") (pinfunction "2_2") (pintype "passive"))
      (node (ref "R22") (pin "1") (pinfunction "1_1") (pintype "passive"))
      (node (ref "U3") (pin "P7") (pinfunction "TDO_P7") (pintype "bidirectional"))
    )
    (net (code "42") (name "TEST") (class "Default")
      (node (ref "J1") (pin "P8") (pinfunction "8_P8") (pintype "bidirectional"))
      (node (ref "U3") (pin "P11") (pinfunction "TEST_P11") (pintype "bidirectional"))
    )
    (net (code "43") (name "TMS") (class "Default")
      (node (ref "J1") (pin "P5") (pinfunction "5_P5") (pintype "bidirectional"))
      (node (ref "U3") (pin "P9") (pinfunction "TMS_P9") (pintype "bidirectional"))
    )
    (net (code "44") (name "TOBLE_TX") (class "Default")
      (node (ref "SV1") (pin "P1") (pinfunction "1_P1") (pintype "passive"))
      (node (ref "U3") (pin "P13") (pinfunction "P2.0/UCATX/MOSI_P13") (pintype "bidirectional"))
      (node (ref "U4") (pin "47") (pinfunction "P28_47") (pintype "bidirectional"))
    )
    (net (code "45") (name "V+") (class "Default")
      (node (ref "C11") (pin "1") (pinfunction "1_1") (pintype "passive"))
      (node (ref "C24") (pin "1") (pinfunction "1_1") (pintype "passive"))
      (node (ref "J4") (pin "1") (pinfunction "VCC_1") (pintype "bidirectional"))
      (node (ref "Q1") (pin "P3") (pinfunction "D_P3") (pintype "passive"))
      (node (ref "U4") (pin "1") (pinfunction "VDD_1") (pintype "bidirectional"))
      (node (ref "U4") (pin "12") (pinfunction "VDD_12") (pintype "bidirectional"))
    )
    (net (code "46") (name "VAMP") (class "Default")
      (node (ref "C39") (pin "1") (pinfunction "1_1") (pintype "passive"))
      (node (ref "R17") (pin "2") (pinfunction "2_2") (pintype "passive"))
      (node (ref "U2") (pin "P4") (pinfunction "OUT_P4") (pintype "bidirectional"))
    )
    (net (code "47") (name "VCC") (class "Default")
      (node (ref "C1") (pin "+") (pinfunction "+_+") (pintype "passive"))
      (node (ref "C3") (pin "1") (pinfunction "1_1") (pintype "passive"))
      (node (ref "C7") (pin "1") (pinfunction "1_1") (pintype "passive"))
      (node (ref "C8") (pin "1") (pinfunction "1_1") (pintype "passive"))
      (node (ref "D2") (pin "C") (pinfunction "C_C") (pintype "passive"))
      (node (ref "R11") (pin "2") (pinfunction "2_2") (pintype "passive"))
      (node (ref "SV1") (pin "P10") (pinfunction "10_P10") (pintype "passive"))
      (node (ref "U1") (pin "P4") (pinfunction "EN_P4") (pintype "bidirectional"))
      (node (ref "U1") (pin "P5") (pinfunction "VIN_P5") (pintype "bidirectional"))
    )
    (net (code "48") (name "VCC_SENSE") (class "Default")
      (node (ref "R11") (pin "1") (pinfunction "1_1") (pintype "passive"))
      (node (ref "R12") (pin "2") (pinfunction "2_2") (pintype "passive"))
      (node (ref "U3") (pin "P6") (pinfunction "P1.5/TB0.2/UCACLK_P6") (pintype "bidirectional"))
    )
    (net (code "49") (name "VFILT") (class "Default")
      (node (ref "C39") (pin "2") (pinfunction "2_2") (pintype "passive"))
      (node (ref "R35") (pin "2") (pinfunction "2_2") (pintype "passive"))
      (node (ref "SV1") (pin "P9") (pinfunction "9_P9") (pintype "passive"))
      (node (ref "U3") (pin "P2") (pinfunction "P1.1/VREF+_P2") (pintype "bidirectional"))
      (node (ref "U7") (pin "P5") (pinfunction "IN+_P5") (pintype "bidirectional"))
    )
    (net (code "50") (name "VS+") (class "Default")
      (node (ref "C10") (pin "1") (pinfunction "1_1") (pintype "passive"))
      (node (ref "C4") (pin "1") (pinfunction "1_1") (pintype "passive"))
      (node (ref "C9") (pin "1") (pinfunction "1_1") (pintype "passive"))
      (node (ref "L1") (pin "1") (pinfunction "1_1") (pintype "passive"))
      (node (ref "R24") (pin "1") (pinfunction "1_1") (pintype "passive"))
      (node (ref "R7") (pin "2") (pinfunction "2_2") (pintype "passive"))
      (node (ref "SV1") (pin "P12") (pinfunction "12_P12") (pintype "passive"))
      (node (ref "U1") (pin "P2") (pinfunction "VOUT_P2") (pintype "bidirectional"))
    )
    (net (code "51") (name "VTEST") (class "Default")
      (node (ref "J2") (pin "PA.3") (pinfunction "P_PA.3") (pintype "bidirectional"))
      (node (ref "R3") (pin "1") (pinfunction "1_1") (pintype "passive"))
      (node (ref "RI1") (pin "1") (pinfunction "1_1") (pintype "passive"))
    )
    (net (code "52") (name "V_SENSE") (class "Default")
      (node (ref "RF") (pin "2") (pinfunction "2_2") (pintype "passive"))
      (node (ref "SV1") (pin "P3") (pinfunction "3_P3") (pintype "passive"))
      (node (ref "U3") (pin "P1") (pinfunction "P1.0/VREF-_P1") (pintype "bidirectional"))
      (node (ref "U6") (pin "P4") (pinfunction "OUT_P4") (pintype "bidirectional"))
    )
    (net (code "53") (name "ZC") (class "Default")
      (node (ref "D1") (pin "C") (pinfunction "C_C") (pintype "passive"))
      (node (ref "D2") (pin "A") (pinfunction "A_A") (pintype "passive"))
      (node (ref "R22") (pin "2") (pinfunction "2_2") (pintype "passive"))
      (node (ref "R3") (pin "2") (pinfunction "2_2") (pintype "passive"))
      (node (ref "SV1") (pin "P11") (pinfunction "11_P11") (pintype "passive"))
    )
    (net (code "54") (name "unconnected-(J1-4-PadP4)") (class "Default")
      (node (ref "J1") (pin "P4") (pinfunction "4_P4") (pintype "bidirectional"))
    )
    (net (code "55") (name "unconnected-(J1-6-PadP6)") (class "Default")
      (node (ref "J1") (pin "P6") (pinfunction "6_P6") (pintype "bidirectional"))
    )
    (net (code "56") (name "unconnected-(J4-SWO-Pad6)") (class "Default")
      (node (ref "J4") (pin "6") (pinfunction "SWO_6") (pintype "bidirectional"))
    )
    (net (code "57") (name "unconnected-(J4-~{RESET}-Pad3)") (class "Default")
      (node (ref "J4") (pin "3") (pinfunction "~{RESET}_3") (pintype "bidirectional"))
    )
    (net (code "58") (name "unconnected-(U4-P00{slash}AREF0-Pad4)") (class "Default")
      (node (ref "U4") (pin "4") (pinfunction "P00/AREF0_4") (pintype "bidirectional"))
    )
    (net (code "59") (name "unconnected-(U4-P01{slash}AIN2-Pad5)") (class "Default")
      (node (ref "U4") (pin "5") (pinfunction "P01/AIN2_5") (pintype "bidirectional"))
    )
    (net (code "60") (name "unconnected-(U4-P02{slash}AIN3-Pad6)") (class "Default")
      (node (ref "U4") (pin "6") (pinfunction "P02/AIN3_6") (pintype "bidirectional"))
    )
    (net (code "61") (name "unconnected-(U4-P03{slash}AIN4-Pad7)") (class "Default")
      (node (ref "U4") (pin "7") (pinfunction "P03/AIN4_7") (pintype "bidirectional"))
    )
    (net (code "62") (name "unconnected-(U4-P04{slash}AIN5-Pad8)") (class "Default")
      (node (ref "U4") (pin "8") (pinfunction "P04/AIN5_8") (pintype "bidirectional"))
    )
    (net (code "63") (name "unconnected-(U4-P06{slash}AIN7{slash}AREF1-Pad10)") (class "Default")
      (node (ref "U4") (pin "10") (pinfunction "P06/AIN7/AREF1_10") (pintype "bidirectional"))
    )
    (net (code "64") (name "unconnected-(U4-P07-Pad11)") (class "Default")
      (node (ref "U4") (pin "11") (pinfunction "P07_11") (pintype "bidirectional"))
    )
    (net (code "65") (name "unconnected-(U4-P08-Pad14)") (class "Default")
      (node (ref "U4") (pin "14") (pinfunction "P08_14") (pintype "bidirectional"))
    )
    (net (code "66") (name "unconnected-(U4-P09-Pad15)") (class "Default")
      (node (ref "U4") (pin "15") (pinfunction "P09_15") (pintype "bidirectional"))
    )
    (net (code "67") (name "unconnected-(U4-P10-Pad16)") (class "Default")
      (node (ref "U4") (pin "16") (pinfunction "P10_16") (pintype "bidirectional"))
    )
    (net (code "68") (name "unconnected-(U4-P11-Pad17)") (class "Default")
      (node (ref "U4") (pin "17") (pinfunction "P11_17") (pintype "bidirectional"))
    )
    (net (code "69") (name "unconnected-(U4-P12-Pad18)") (class "Default")
      (node (ref "U4") (pin "18") (pinfunction "P12_18") (pintype "bidirectional"))
    )
    (net (code "70") (name "unconnected-(U4-P13-Pad19)") (class "Default")
      (node (ref "U4") (pin "19") (pinfunction "P13_19") (pintype "bidirectional"))
    )
    (net (code "71") (name "unconnected-(U4-P14-Pad20)") (class "Default")
      (node (ref "U4") (pin "20") (pinfunction "P14_20") (pintype "bidirectional"))
    )
    (net (code "72") (name "unconnected-(U4-P15-Pad21)") (class "Default")
      (node (ref "U4") (pin "21") (pinfunction "P15_21") (pintype "bidirectional"))
    )
    (net (code "73") (name "unconnected-(U4-P16-Pad22)") (class "Default")
      (node (ref "U4") (pin "22") (pinfunction "P16_22") (pintype "bidirectional"))
    )
    (net (code "74") (name "unconnected-(U4-P17-Pad25)") (class "Default")
      (node (ref "U4") (pin "25") (pinfunction "P17_25") (pintype "bidirectional"))
    )
    (net (code "75") (name "unconnected-(U4-P18-Pad26)") (class "Default")
      (node (ref "U4") (pin "26") (pinfunction "P18_26") (pintype "bidirectional"))
    )
    (net (code "76") (name "unconnected-(U4-P19-Pad27)") (class "Default")
      (node (ref "U4") (pin "27") (pinfunction "P19_27") (pintype "bidirectional"))
    )
    (net (code "77") (name "unconnected-(U4-P20-Pad28)") (class "Default")
      (node (ref "U4") (pin "28") (pinfunction "P20_28") (pintype "bidirectional"))
    )
    (net (code "78") (name "unconnected-(U4-P21-Pad40)") (class "Default")
      (node (ref "U4") (pin "40") (pinfunction "P21_40") (pintype "bidirectional"))
    )
    (net (code "79") (name "unconnected-(U4-P22-Pad41)") (class "Default")
      (node (ref "U4") (pin "41") (pinfunction "P22_41") (pintype "bidirectional"))
    )
    (net (code "80") (name "unconnected-(U4-P23-Pad42)") (class "Default")
      (node (ref "U4") (pin "42") (pinfunction "P23_42") (pintype "bidirectional"))
    )
    (net (code "81") (name "unconnected-(U4-P24-Pad43)") (class "Default")
      (node (ref "U4") (pin "43") (pinfunction "P24_43") (pintype "bidirectional"))
    )
    (net (code "82") (name "unconnected-(U4-P25-Pad44)") (class "Default")
      (node (ref "U4") (pin "44") (pinfunction "P25_44") (pintype "bidirectional"))
    )
    (net (code "83") (name "unconnected-(U4-P26{slash}AIN0{slash}XL2-Pad45)") (class "Default")
      (node (ref "U4") (pin "45") (pinfunction "P26/AIN0/XL2_45") (pintype "bidirectional"))
    )
    (net (code "84") (name "unconnected-(U4-P30-Pad3)") (class "Default")
      (node (ref "U4") (pin "3") (pinfunction "P30_3") (pintype "bidirectional"))
    )
  )
)
